# Plugs.net
KiCad netlist of a schematic drawn in Altium Designer
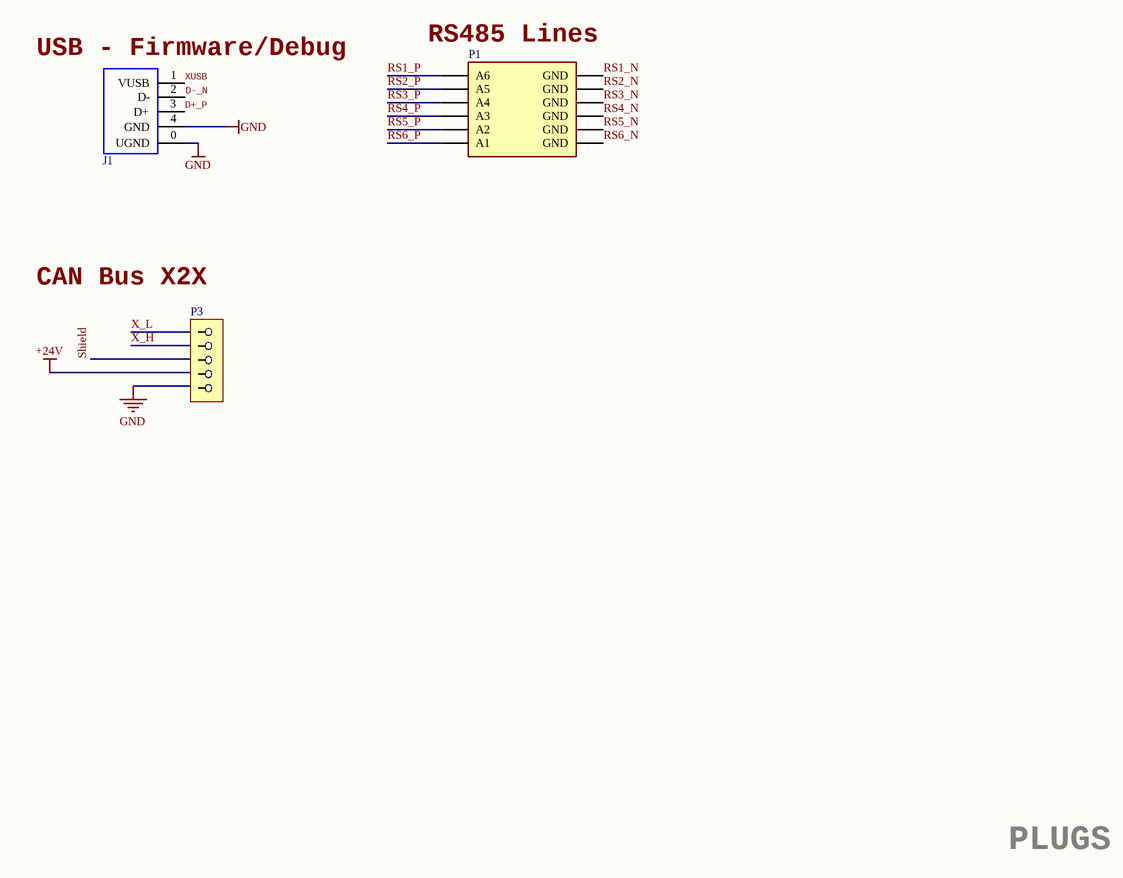
[diagram p0: Plugs.SchDoc]

(export (version "E")
  (design (tool "Eeschema 10.0.6"))
  (components
    (comp (ref "J1")
      (value "~")
      (footprint "USB B")
      (fields (field (name "PART NUMBER") "USBB-1J"))
      (libsource (lib "kontr") (part "USBB-1J"))
    )
    (comp (ref "P1")
      (value "~")
      (footprint "МЦТР.00010572.00.0011:mcd 1,5/6-G1-3.81")
      (fields (field (name "PART NUMBER") "MCD 1.5/6-G1-3.81"))
      (libsource (lib "kontr") (part "Header 6X2"))
    )
    (comp (ref "P3")
      (value "~")
      (footprint "PhClass5")
      (fields (field (name "PART NUMBER") "EMSTBA 2.5/5-G-5.08"))
      (libsource (lib "kontr") (part "EMSTBA 2.5/5-G-5.08"))
    )
  )
  (nets
    (net (code "1") (name "+24V") (class "Default")
      (node (ref "P3") (pin "4") (pinfunction "2_4") (pintype "passive"))
    )
    (net (code "2") (name "/D+_P") (class "Default")
      (node (ref "J1") (pin "3") (pinfunction "D+_3") (pintype "passive"))
    )
    (net (code "3") (name "/D-_N") (class "Default")
      (node (ref "J1") (pin "2") (pinfunction "D-_2") (pintype "passive"))
    )
    (net (code "4") (name "/RS1_N") (class "Default")
      (node (ref "P1") (pin "2") (pinfunction "GND_2") (pintype "passive"))
    )
    (net (code "5") (name "/RS1_P") (class "Default")
      (node (ref "P1") (pin "1") (pinfunction "A6_1") (pintype "passive"))
    )
    (net (code "6") (name "/RS2_N") (class "Default")
      (node (ref "P1") (pin "4") (pinfunction "GND_4") (pintype "passive"))
    )
    (net (code "7") (name "/RS2_P") (class "Default")
      (node (ref "P1") (pin "3") (pinfunction "A5_3") (pintype "passive"))
    )
    (net (code "8") (name "/RS3_N") (class "Default")
      (node (ref "P1") (pin "6") (pinfunction "GND_6") (pintype "passive"))
    )
    (net (code "9") (name "/RS3_P") (class "Default")
      (node (ref "P1") (pin "5") (pinfunction "A4_5") (pintype "passive"))
    )
    (net (code "10") (name "/RS4_N") (class "Default")
      (node (ref "P1") (pin "8") (pinfunction "GND_8") (pintype "passive"))
    )
    (net (code "11") (name "/RS4_P") (class "Default")
      (node (ref "P1") (pin "7") (pinfunction "A3_7") (pintype "passive"))
    )
    (net (code "12") (name "/RS5_N") (class "Default")
      (node (ref "P1") (pin "10") (pinfunction "GND_10") (pintype "passive"))
    )
    (net (code "13") (name "/RS5_P") (class "Default")
      (node (ref "P1") (pin "9") (pinfunction "A2_9") (pintype "passive"))
    )
    (net (code "14") (name "/RS6_N") (class "Default")
      (node (ref "P1") (pin "12") (pinfunction "GND_12") (pintype "passive"))
    )
    (net (code "15") (name "/RS6_P") (class "Default")
      (node (ref "P1") (pin "11") (pinfunction "A1_11") (pintype "passive"))
    )
    (net (code "16") (name "/Shield") (class "Default")
      (node (ref "P3") (pin "3") (pinfunction "3_3") (pintype "passive"))
    )
    (net (code "17") (name "/XUSB") (class "Default")
      (node (ref "J1") (pin "1") (pinfunction "VUSB_1") (pintype "passive"))
    )
    (net (code "18") (name "/X_H") (class "Default")
      (node (ref "P3") (pin "2") (pinfunction "2_2") (pintype "passive"))
    )
    (net (code "19") (name "/X_L") (class "Default")
      (node (ref "P3") (pin "1") (pinfunction "1_1") (pintype "passive"))
    )
    (net (code "20") (name "GND") (class "Default")
      (node (ref "J1") (pin "0") (pinfunction "UGND_0") (pintype "passive"))
      (node (ref "J1") (pin "4") (pinfunction "GND_4") (pintype "passive"))
      (node (ref "P3") (pin "5") (pinfunction "3_5") (pintype "passive"))
    )
  )
)
